# ProProject_Buck-Boost_1_2024-04-13.net
KiCad netlist of a schematic drawn in EasyEDA Pro
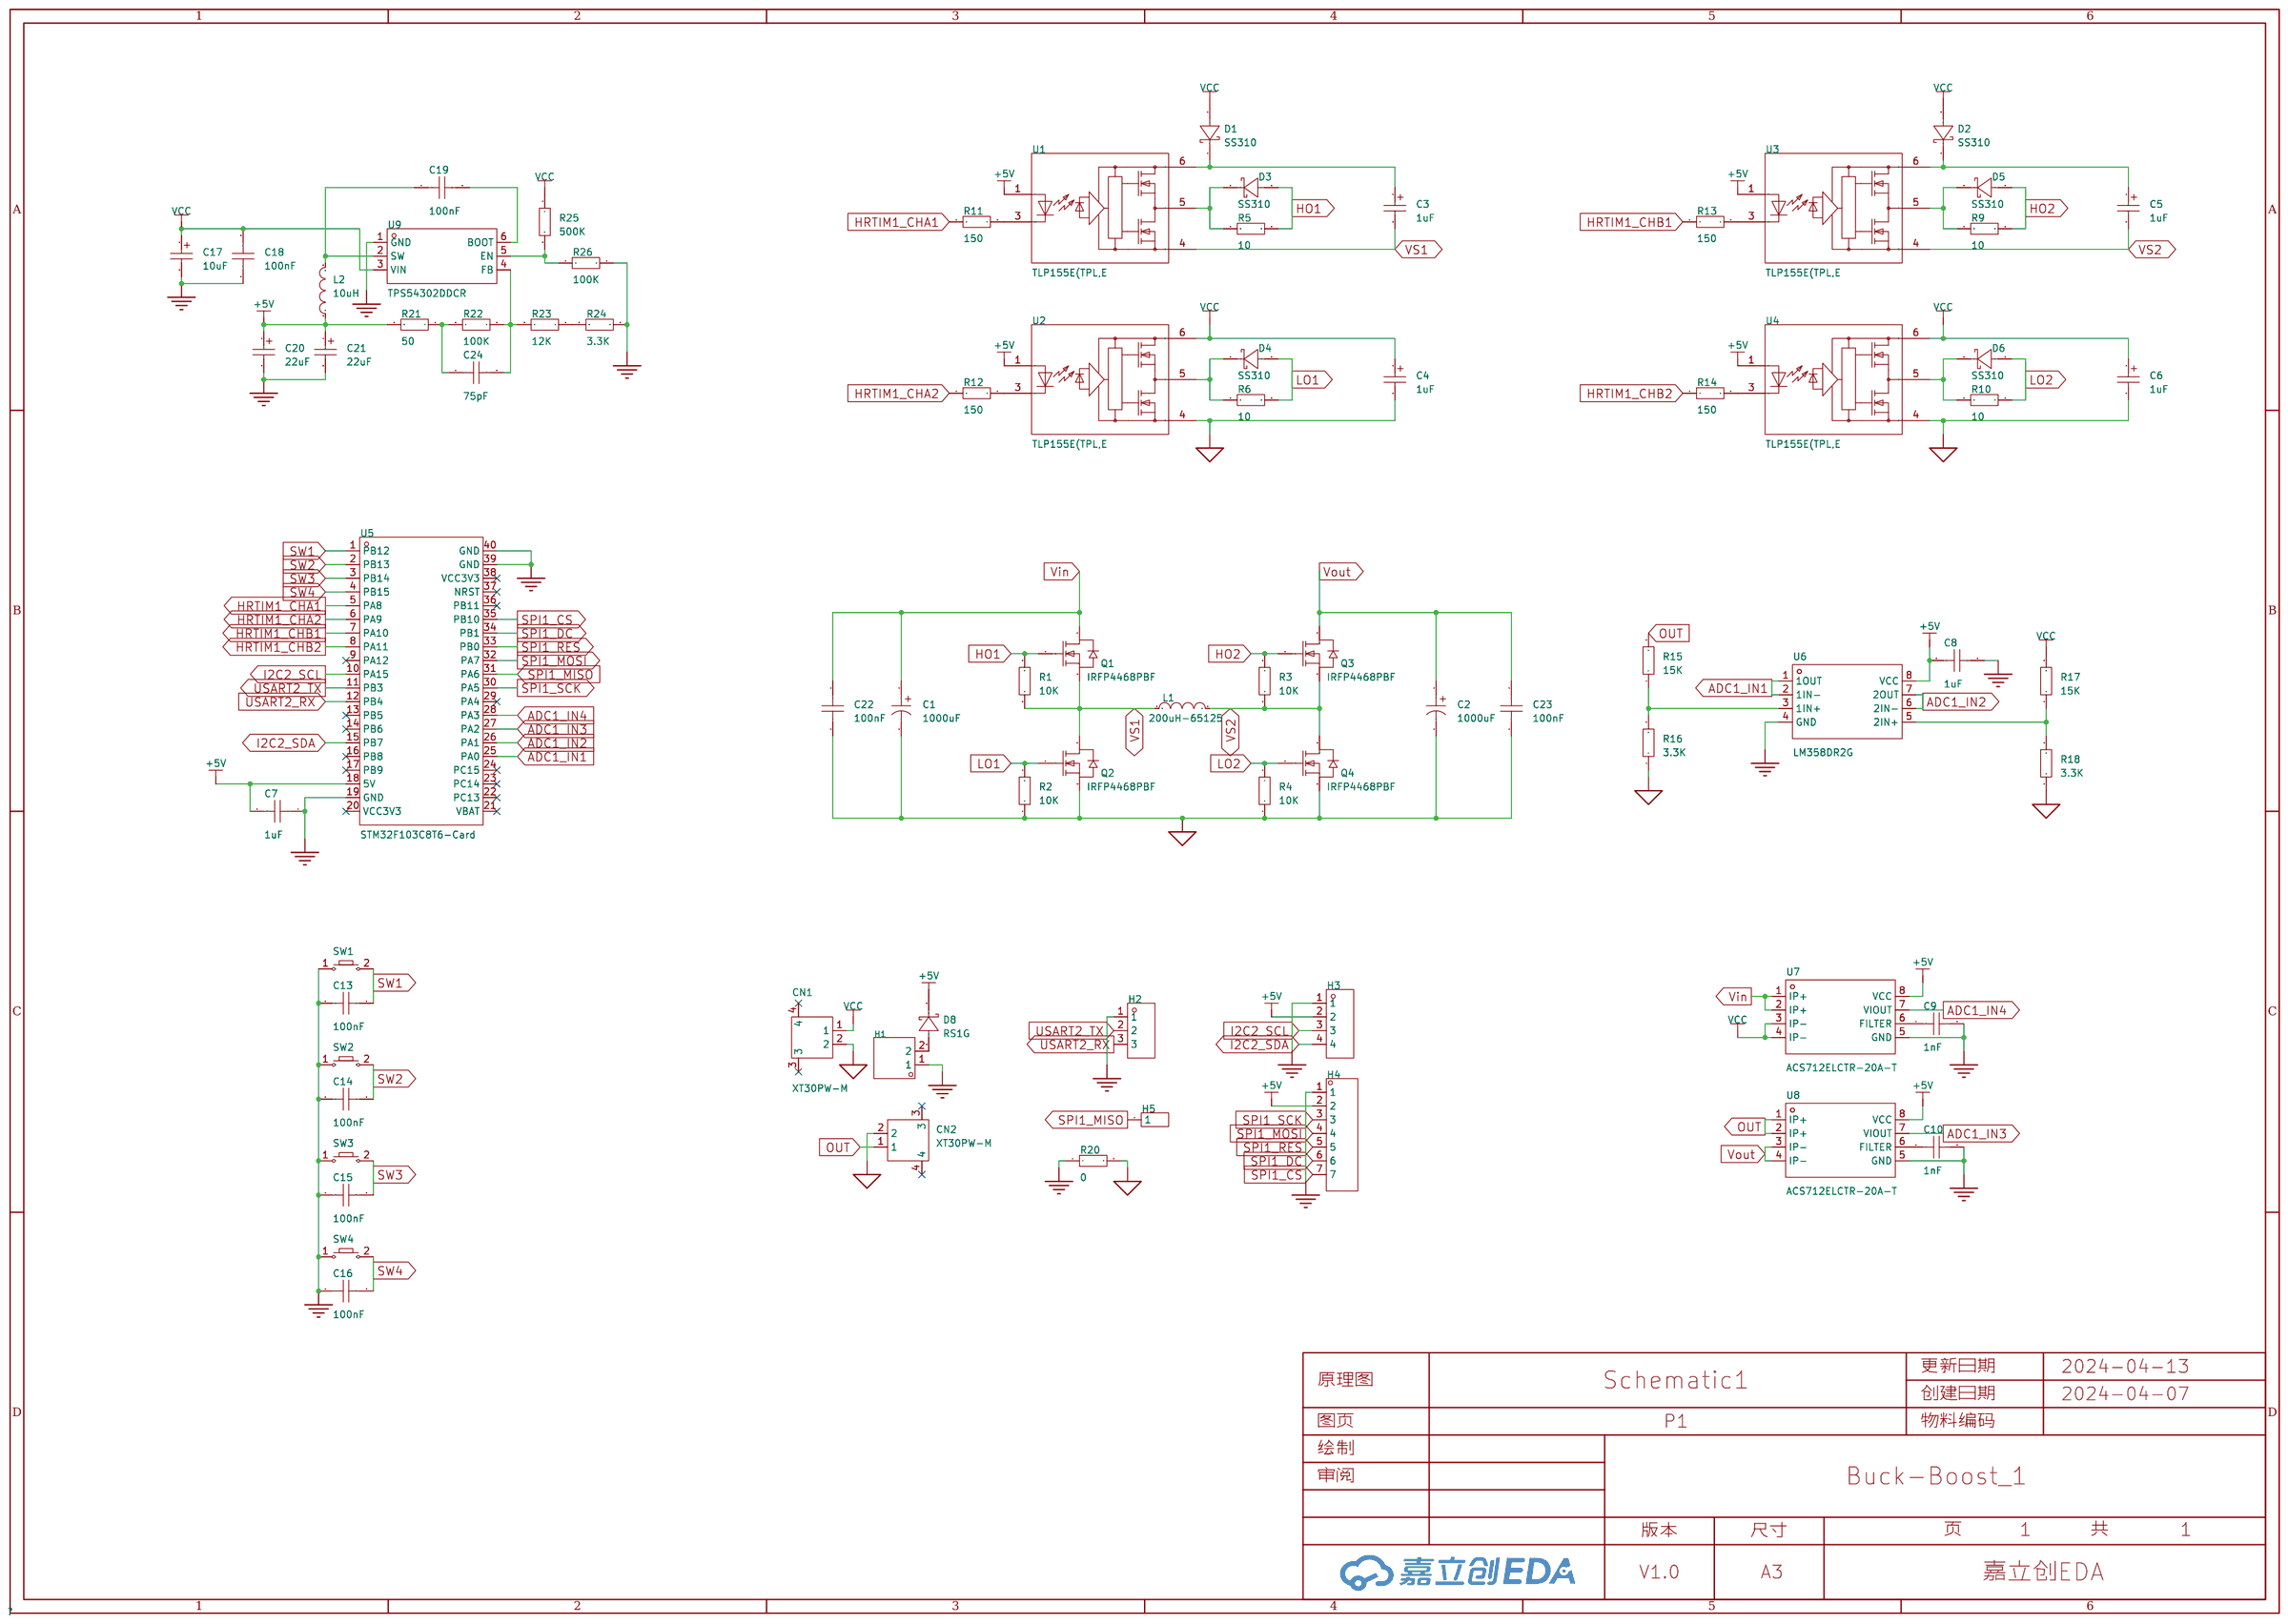
[diagram p0: schematic sheet]

(export (version "E")
  (design (tool "Eeschema 10.0.6"))
  (components
    (comp (ref "C1")
      (value "1000uF")
      (footprint "easyedapro:CAP-TH_BD16.0-P7.50-D1.5-FD")
      (description "容值:470uF;精度:±20%;额定电压:120V;纹波电流:-;等效串联电阻:-;")
      (fields (field (name "Manufacturer Part") "KF102M050I250A") (field (name "Manufacturer") "CapXon(丰宾)"))
      (libsource (lib "easyedapro") (part "ERS2BM471L35OT"))
    )
    (comp (ref "C2")
      (value "1000uF")
      (footprint "easyedapro:CAP-TH_BD16.0-P7.50-D1.5-FD")
      (description "容值:470uF;精度:±20%;额定电压:120V;纹波电流:-;等效串联电阻:-;")
      (fields (field (name "Manufacturer Part") "KF102M050I250A") (field (name "Manufacturer") "CapXon(丰宾)"))
      (libsource (lib "easyedapro") (part "ERS2BM471L35OT"))
    )
    (comp (ref "C3")
      (value "1uF")
      (footprint "easyedapro:CASE-A_3216")
      (description "容值:1uF;精度:±10%;额定电压:35V;等效串联电阻:7.5Ω@100kHz;")
      (fields (field (name "Manufacturer Part") "TAJA105K035RNJ") (field (name "Manufacturer") "Kyocera AVX"))
      (libsource (lib "easyedapro") (part "TAJA105K035RNJ"))
    )
    (comp (ref "C4")
      (value "1uF")
      (footprint "easyedapro:CASE-A_3216")
      (description "容值:1uF;精度:±10%;额定电压:35V;等效串联电阻:7.5Ω@100kHz;")
      (fields (field (name "Manufacturer Part") "TAJA105K035RNJ") (field (name "Manufacturer") "Kyocera AVX"))
      (libsource (lib "easyedapro") (part "TAJA105K035RNJ"))
    )
    (comp (ref "C5")
      (value "1uF")
      (footprint "easyedapro:CASE-A_3216")
      (description "容值:1uF;精度:±10%;额定电压:35V;等效串联电阻:7.5Ω@100kHz;")
      (fields (field (name "Manufacturer Part") "TAJA105K035RNJ") (field (name "Manufacturer") "Kyocera AVX"))
      (libsource (lib "easyedapro") (part "TAJA105K035RNJ"))
    )
    (comp (ref "C6")
      (value "1uF")
      (footprint "easyedapro:CASE-A_3216")
      (description "容值:1uF;精度:±10%;额定电压:35V;等效串联电阻:7.5Ω@100kHz;")
      (fields (field (name "Manufacturer Part") "TAJA105K035RNJ") (field (name "Manufacturer") "Kyocera AVX"))
      (libsource (lib "easyedapro") (part "TAJA105K035RNJ"))
    )
    (comp (ref "C7")
      (value "1uF")
      (footprint "easyedapro:C0805")
      (libsource (lib "easyedapro") (part "CapAcitance"))
    )
    (comp (ref "C8")
      (value "1uF")
      (footprint "easyedapro:C0805")
      (libsource (lib "easyedapro") (part "CapAcitance"))
    )
    (comp (ref "C9")
      (value "1nF")
      (footprint "easyedapro:C0805")
      (libsource (lib "easyedapro") (part "CapAcitance"))
    )
    (comp (ref "C10")
      (value "1nF")
      (footprint "easyedapro:C0805")
      (libsource (lib "easyedapro") (part "CapAcitance"))
    )
    (comp (ref "C13")
      (value "100nF")
      (footprint "easyedapro:C0805")
      (libsource (lib "easyedapro") (part "CapAcitance"))
    )
    (comp (ref "C14")
      (value "100nF")
      (footprint "easyedapro:C0805")
      (libsource (lib "easyedapro") (part "CapAcitance"))
    )
    (comp (ref "C15")
      (value "100nF")
      (footprint "easyedapro:C0805")
      (libsource (lib "easyedapro") (part "CapAcitance"))
    )
    (comp (ref "C16")
      (value "100nF")
      (footprint "easyedapro:C0805")
      (libsource (lib "easyedapro") (part "CapAcitance"))
    )
    (comp (ref "C17")
      (value "10uF")
      (footprint "easyedapro:CAP-SMD_L3.5-W2.8-R-RD")
      (description "容值:10uF;精度:±10%;额定电压:25V;等效串联电阻:2.5Ω@100kHz;")
      (fields (field (name "Manufacturer Part") "TAJB106K025RNJ") (field (name "Manufacturer") "Kyocera AVX"))
      (libsource (lib "easyedapro") (part "TAJB106K025RNJ"))
    )
    (comp (ref "C18")
      (value "100nF")
      (footprint "easyedapro:C0805")
      (libsource (lib "easyedapro") (part "CapAcitance"))
    )
    (comp (ref "C19")
      (value "100nF")
      (footprint "easyedapro:C0805")
      (libsource (lib "easyedapro") (part "CapAcitance"))
    )
    (comp (ref "C20")
      (value "22uF")
      (footprint "easyedapro:CASE-B_3528")
      (description "容值:22uF;精度:±10%;额定电压:16V;等效串联电阻:2.3Ω@100kHz;")
      (fields (field (name "Manufacturer Part") "TAJB226K016RNJ") (field (name "Manufacturer") "Kyocera AVX"))
      (libsource (lib "easyedapro") (part "TAJB226K016RNJ"))
    )
    (comp (ref "C21")
      (value "22uF")
      (footprint "easyedapro:CASE-B_3528")
      (description "容值:22uF;精度:±10%;额定电压:16V;等效串联电阻:2.3Ω@100kHz;")
      (fields (field (name "Manufacturer Part") "TAJB226K016RNJ") (field (name "Manufacturer") "Kyocera AVX"))
      (libsource (lib "easyedapro") (part "TAJB226K016RNJ"))
    )
    (comp (ref "C22")
      (value "100nF")
      (footprint "easyedapro:C0805")
      (libsource (lib "easyedapro") (part "CapAcitance"))
    )
    (comp (ref "C23")
      (value "100nF")
      (footprint "easyedapro:C0805")
      (libsource (lib "easyedapro") (part "CapAcitance"))
    )
    (comp (ref "C24")
      (value "75pF")
      (footprint "easyedapro:C0805")
      (libsource (lib "easyedapro") (part "CapAcitance"))
    )
    (comp (ref "CN1")
      (value "XT30PW-M")
      (footprint "easyedapro:CONN-TH_XT30PW-M")
      (description "类别:-;类型1:-;")
      (fields (field (name "Manufacturer") "AMASS(艾迈斯)"))
      (libsource (lib "easyedapro") (part "XT30PW-M"))
    )
    (comp (ref "CN2")
      (value "XT30PW-M")
      (footprint "easyedapro:CONN-TH_XT30PW-M")
      (description "类别:-;类型1:-;")
      (fields (field (name "Manufacturer") "AMASS(艾迈斯)"))
      (libsource (lib "easyedapro") (part "XT30PW-M"))
    )
    (comp (ref "D1")
      (value "SS310")
      (footprint "easyedapro:SMC_L6.9-W5.9-LS7.9-RD")
      (fields (field (name "Manufacturer") "MDD"))
      (libsource (lib "easyedapro") (part "SS56_C5161914"))
    )
    (comp (ref "D2")
      (value "SS310")
      (footprint "easyedapro:SMC_L6.9-W5.9-LS7.9-RD")
      (fields (field (name "Manufacturer") "MDD"))
      (libsource (lib "easyedapro") (part "SS56_C5161914"))
    )
    (comp (ref "D3")
      (value "SS310")
      (footprint "easyedapro:SMC_L6.9-W5.9-LS7.9-RD")
      (fields (field (name "Manufacturer") "MDD"))
      (libsource (lib "easyedapro") (part "SS56_C5161914"))
    )
    (comp (ref "D4")
      (value "SS310")
      (footprint "easyedapro:SMC_L6.9-W5.9-LS7.9-RD")
      (fields (field (name "Manufacturer") "MDD"))
      (libsource (lib "easyedapro") (part "SS56_C5161914"))
    )
    (comp (ref "D5")
      (value "SS310")
      (footprint "easyedapro:SMC_L6.9-W5.9-LS7.9-RD")
      (fields (field (name "Manufacturer") "MDD"))
      (libsource (lib "easyedapro") (part "SS56_C5161914"))
    )
    (comp (ref "D6")
      (value "SS310")
      (footprint "easyedapro:SMC_L6.9-W5.9-LS7.9-RD")
      (fields (field (name "Manufacturer") "MDD"))
      (libsource (lib "easyedapro") (part "SS56_C5161914"))
    )
    (comp (ref "D8")
      (value "RS1G")
      (footprint "easyedapro:SMC_L6.9-W5.9-LS7.9-RD")
      (fields (field (name "Manufacturer") "宏迦橙"))
      (libsource (lib "easyedapro") (part "SS56_C5161914"))
    )
    (comp (ref "H1")
      (value "~")
      (footprint "easyedapro:HDR-TH_2P-P2.54-V-M-1")
      (libsource (lib "easyedapro") (part "210S-1*2P L=11.6MMGold-plated black"))
    )
    (comp (ref "H2")
      (value "~")
      (footprint "easyedapro:HDR-TH_3P-P2.54-V-M")
      (libsource (lib "easyedapro") (part "PZ254V-11-03P_C2937625"))
    )
    (comp (ref "H3")
      (value "~")
      (footprint "easyedapro:HDR-TH_4P-P2.54-V-F")
      (libsource (lib "easyedapro") (part "2.54-1*4P母"))
    )
    (comp (ref "H4")
      (value "~")
      (footprint "easyedapro:HDR-TH_7P-P2.54-V-F")
      (libsource (lib "easyedapro") (part "220S-1*7P H=8.5MM Ytype Gold-plated"))
    )
    (comp (ref "H5")
      (value "~")
      (footprint "easyedapro:HDR-TH_1P-V-M_XKB_X4611WV-01I-C28D40")
      (libsource (lib "easyedapro") (part "HDR_1x1"))
    )
    (comp (ref "L1")
      (value "200uH-65125")
      (footprint "easyedapro:IND-TH_200UH-65125")
      (libsource (lib "easyedapro") (part "200UH-65125"))
    )
    (comp (ref "L2")
      (value "10uH")
      (footprint "easyedapro:IND-SMD_L7.3-W6.8")
      (description "电感值:10uH;精度:±20%;额定电流:4.5A;饱和电流(Isat):5.5A;类型:一体成型电感;")
      (fields (field (name "Manufacturer Part") "FXL0420-100-M") (field (name "Manufacturer") "cjiang(长江微电)"))
      (libsource (lib "easyedapro") (part "FXL0630-100-M"))
    )
    (comp (ref "Q1")
      (value "IRFP4468PBF")
      (footprint "easyedapro:TO-247AC-3_L15.8-W5.0-P5.46-L")
      (fields (field (name "Manufacturer") "Infineon(英飞凌)"))
      (libsource (lib "easyedapro") (part "IRFP4468PBF"))
    )
    (comp (ref "Q2")
      (value "IRFP4468PBF")
      (footprint "easyedapro:TO-247AC-3_L15.8-W5.0-P5.46-L")
      (fields (field (name "Manufacturer") "Infineon(英飞凌)"))
      (libsource (lib "easyedapro") (part "IRFP4468PBF"))
    )
    (comp (ref "Q3")
      (value "IRFP4468PBF")
      (footprint "easyedapro:TO-247AC-3_L15.8-W5.0-P5.46-L")
      (fields (field (name "Manufacturer") "Infineon(英飞凌)"))
      (libsource (lib "easyedapro") (part "IRFP4468PBF"))
    )
    (comp (ref "Q4")
      (value "IRFP4468PBF")
      (footprint "easyedapro:TO-247AC-3_L15.8-W5.0-P5.46-L")
      (fields (field (name "Manufacturer") "Infineon(英飞凌)"))
      (libsource (lib "easyedapro") (part "IRFP4468PBF"))
    )
    (comp (ref "R1") (value "10K") (footprint "easyedapro:R0805") (libsource (lib "easyedapro") (part "电阻")))
    (comp (ref "R2") (value "10K") (footprint "easyedapro:R0805") (libsource (lib "easyedapro") (part "电阻")))
    (comp (ref "R3") (value "10K") (footprint "easyedapro:R0805") (libsource (lib "easyedapro") (part "电阻")))
    (comp (ref "R4") (value "10K") (footprint "easyedapro:R0805") (libsource (lib "easyedapro") (part "电阻")))
    (comp (ref "R5") (value "10") (footprint "easyedapro:R0805") (libsource (lib "easyedapro") (part "电阻")))
    (comp (ref "R6") (value "10") (footprint "easyedapro:R0805") (libsource (lib "easyedapro") (part "电阻")))
    (comp (ref "R9") (value "10") (footprint "easyedapro:R0805") (libsource (lib "easyedapro") (part "电阻")))
    (comp (ref "R10") (value "10") (footprint "easyedapro:R0805") (libsource (lib "easyedapro") (part "电阻")))
    (comp (ref "R11") (value "150") (footprint "easyedapro:R0805") (libsource (lib "easyedapro") (part "电阻")))
    (comp (ref "R12") (value "150") (footprint "easyedapro:R0805") (libsource (lib "easyedapro") (part "电阻")))
    (comp (ref "R13") (value "150") (footprint "easyedapro:R0805") (libsource (lib "easyedapro") (part "电阻")))
    (comp (ref "R14") (value "150") (footprint "easyedapro:R0805") (libsource (lib "easyedapro") (part "电阻")))
    (comp (ref "R15") (value "15K") (footprint "easyedapro:R0805") (libsource (lib "easyedapro") (part "电阻")))
    (comp (ref "R16")
      (value "3.3K")
      (footprint "easyedapro:R0805")
      (libsource (lib "easyedapro") (part "电阻"))
    )
    (comp (ref "R17") (value "15K") (footprint "easyedapro:R0805") (libsource (lib "easyedapro") (part "电阻")))
    (comp (ref "R18")
      (value "3.3K")
      (footprint "easyedapro:R0805")
      (libsource (lib "easyedapro") (part "电阻"))
    )
    (comp (ref "R20") (value "0") (footprint "easyedapro:R0805") (libsource (lib "easyedapro") (part "电阻")))
    (comp (ref "R21") (value "50") (footprint "easyedapro:R0805") (libsource (lib "easyedapro") (part "电阻")))
    (comp (ref "R22")
      (value "100K")
      (footprint "easyedapro:R0805")
      (libsource (lib "easyedapro") (part "电阻"))
    )
    (comp (ref "R23") (value "12K") (footprint "easyedapro:R0805") (libsource (lib "easyedapro") (part "电阻")))
    (comp (ref "R24")
      (value "3.3K")
      (footprint "easyedapro:R0805")
      (libsource (lib "easyedapro") (part "电阻"))
    )
    (comp (ref "R25")
      (value "500K")
      (footprint "easyedapro:R0805")
      (libsource (lib "easyedapro") (part "电阻"))
    )
    (comp (ref "R26")
      (value "100K")
      (footprint "easyedapro:R0805")
      (libsource (lib "easyedapro") (part "电阻"))
    )
    (comp (ref "SW1")
      (value "~")
      (footprint "easyedapro:Key_SMD_3x4x2")
      (libsource (lib "easyedapro") (part "轻触按键x2"))
    )
    (comp (ref "SW2")
      (value "~")
      (footprint "easyedapro:Key_SMD_3x4x2")
      (libsource (lib "easyedapro") (part "轻触按键x2"))
    )
    (comp (ref "SW3")
      (value "~")
      (footprint "easyedapro:Key_SMD_3x4x2")
      (libsource (lib "easyedapro") (part "轻触按键x2"))
    )
    (comp (ref "SW4")
      (value "~")
      (footprint "easyedapro:Key_SMD_3x4x2")
      (libsource (lib "easyedapro") (part "轻触按键x2"))
    )
    (comp (ref "U1")
      (value "TLP155E(TPL,E")
      (footprint "easyedapro:OPTO-SMD-5_L3.7-W4.6-P1.27-LS7.0-BR")
      (description "输入类型:DC;电源电压:10V~30V;共模瞬变抗扰度CMTI:15kV/us;传播延迟tpLH/tpHL:170ns；170ns;")
      (fields (field (name "Manufacturer") "TOSHIBA(东芝)"))
      (libsource (lib "easyedapro") (part "TLP155E(TPL,E"))
    )
    (comp (ref "U2")
      (value "TLP155E(TPL,E")
      (footprint "easyedapro:OPTO-SMD-5_L3.7-W4.6-P1.27-LS7.0-BR")
      (description "输入类型:DC;电源电压:10V~30V;共模瞬变抗扰度CMTI:15kV/us;传播延迟tpLH/tpHL:170ns；170ns;")
      (fields (field (name "Manufacturer") "TOSHIBA(东芝)"))
      (libsource (lib "easyedapro") (part "TLP155E(TPL,E"))
    )
    (comp (ref "U3")
      (value "TLP155E(TPL,E")
      (footprint "easyedapro:OPTO-SMD-5_L3.7-W4.6-P1.27-LS7.0-BR")
      (description "输入类型:DC;电源电压:10V~30V;共模瞬变抗扰度CMTI:15kV/us;传播延迟tpLH/tpHL:170ns；170ns;")
      (fields (field (name "Manufacturer") "TOSHIBA(东芝)"))
      (libsource (lib "easyedapro") (part "TLP155E(TPL,E"))
    )
    (comp (ref "U4")
      (value "TLP155E(TPL,E")
      (footprint "easyedapro:OPTO-SMD-5_L3.7-W4.6-P1.27-LS7.0-BR")
      (description "输入类型:DC;电源电压:10V~30V;共模瞬变抗扰度CMTI:15kV/us;传播延迟tpLH/tpHL:170ns；170ns;")
      (fields (field (name "Manufacturer") "TOSHIBA(东芝)"))
      (libsource (lib "easyedapro") (part "TLP155E(TPL,E"))
    )
    (comp (ref "U5")
      (value "STM32F103C8T6-Card")
      (footprint "easyedapro:CONN-TH_L53.3-W22.9_STM32F103C8T6-CARD")
      (libsource (lib "easyedapro") (part "STM32F103C8T6-CARD"))
    )
    (comp (ref "U6")
      (value "LM358DR2G")
      (footprint "easyedapro:SOIC-8_L5.0-W4.0-P1.27-LS6.0-BL")
      (description "放大器数:双路;增益带宽积(GBP):1MHz;输入偏置电流(Ib):45nA;压摆率(SR):-;带宽(-3db):-;")
      (fields (field (name "Manufacturer") "onsemi(安森美)"))
      (libsource (lib "easyedapro") (part "LM358DR2G"))
    )
    (comp (ref "U7")
      (value "ACS712ELCTR-20A-T")
      (footprint "easyedapro:SOIC-8_L4.9-W3.9-P1.27-LS6.0-BL")
      (description "电流测量范围:20A;灵敏度:100mV/A;")
      (fields (field (name "Manufacturer") "ALLEGRO(美国埃戈罗)"))
      (libsource (lib "easyedapro") (part "ACS712ELCTR-20A-T"))
    )
    (comp (ref "U8")
      (value "ACS712ELCTR-20A-T")
      (footprint "easyedapro:SOIC-8_L4.9-W3.9-P1.27-LS6.0-BL")
      (description "电流测量范围:20A;灵敏度:100mV/A;")
      (fields (field (name "Manufacturer") "ALLEGRO(美国埃戈罗)"))
      (libsource (lib "easyedapro") (part "ACS712ELCTR-20A-T"))
    )
    (comp (ref "U9")
      (value "TPS54302DDCR")
      (footprint "easyedapro:SOT-23-6_L2.9-W1.6-P0.95-LS2.8-BL")
      (description "功能类型:降压型;输出类型:可调;输入电压:4.5V~28V;输出电压:596mV~28V;输出电流(最大值):3A;")
      (fields (field (name "Manufacturer") "TI(德州仪器)"))
      (libsource (lib "easyedapro") (part "TPS54302DDCR_C311983"))
    )
  )
  (nets
    (net (code "1") (name "+5V") (class "Default")
      (node (ref "C20") (pin "1") (pinfunction "1_1") (pintype "input"))
      (node (ref "C21") (pin "1") (pinfunction "1_1") (pintype "input"))
      (node (ref "C7") (pin "2") (pinfunction "2_2") (pintype "input"))
      (node (ref "C8") (pin "1") (pinfunction "1_1") (pintype "input"))
      (node (ref "D8") (pin "1") (pinfunction "K_1") (pintype "unspecified"))
      (node (ref "H3") (pin "2") (pinfunction "2_2") (pintype "unspecified"))
      (node (ref "H4") (pin "2") (pinfunction "2_2") (pintype "unspecified"))
      (node (ref "L2") (pin "1") (pinfunction "1_1") (pintype "unspecified"))
      (node (ref "R21") (pin "2") (pinfunction "2_2") (pintype "input"))
      (node (ref "U1") (pin "1") (pinfunction "AN_1") (pintype "unspecified"))
      (node (ref "U2") (pin "1") (pinfunction "AN_1") (pintype "unspecified"))
      (node (ref "U3") (pin "1") (pinfunction "AN_1") (pintype "unspecified"))
      (node (ref "U4") (pin "1") (pinfunction "AN_1") (pintype "unspecified"))
      (node (ref "U5") (pin "18") (pinfunction "5V_18") (pintype "unspecified"))
      (node (ref "U6") (pin "8") (pinfunction "VCC_8") (pintype "unspecified"))
      (node (ref "U7") (pin "8") (pinfunction "VCC_8") (pintype "unspecified"))
      (node (ref "U8") (pin "8") (pinfunction "VCC_8") (pintype "unspecified"))
    )
    (net (code "2") (name "ADC1_IN1") (class "Default")
      (node (ref "U5") (pin "25") (pinfunction "PA0_25") (pintype "unspecified"))
      (node (ref "U6") (pin "1") (pinfunction "1OUT_1") (pintype "unspecified"))
      (node (ref "U6") (pin "2") (pinfunction "1IN-_2") (pintype "unspecified"))
    )
    (net (code "3") (name "ADC1_IN2") (class "Default")
      (node (ref "U5") (pin "26") (pinfunction "PA1_26") (pintype "unspecified"))
      (node (ref "U6") (pin "6") (pinfunction "2IN-_6") (pintype "unspecified"))
      (node (ref "U6") (pin "7") (pinfunction "2OUT_7") (pintype "unspecified"))
    )
    (net (code "4") (name "ADC1_IN3") (class "Default")
      (node (ref "U5") (pin "27") (pinfunction "PA2_27") (pintype "unspecified"))
      (node (ref "U8") (pin "7") (pinfunction "VIOUT_7") (pintype "unspecified"))
    )
    (net (code "5") (name "ADC1_IN4") (class "Default")
      (node (ref "U5") (pin "28") (pinfunction "PA3_28") (pintype "unspecified"))
      (node (ref "U7") (pin "7") (pinfunction "VIOUT_7") (pintype "unspecified"))
    )
    (net (code "6") (name "AGND") (class "Default")
      (node (ref "C1") (pin "2") (pinfunction "2_2") (pintype "input"))
      (node (ref "C2") (pin "2") (pinfunction "2_2") (pintype "input"))
      (node (ref "C22") (pin "2") (pinfunction "2_2") (pintype "input"))
      (node (ref "C23") (pin "2") (pinfunction "2_2") (pintype "input"))
      (node (ref "C4") (pin "2") (pinfunction "2_2") (pintype "input"))
      (node (ref "C6") (pin "2") (pinfunction "2_2") (pintype "input"))
      (node (ref "CN1") (pin "2") (pinfunction "2_2") (pintype "unspecified"))
      (node (ref "CN2") (pin "2") (pinfunction "2_2") (pintype "unspecified"))
      (node (ref "Q2") (pin "3") (pinfunction "S_3") (pintype "unspecified"))
      (node (ref "Q4") (pin "3") (pinfunction "S_3") (pintype "unspecified"))
      (node (ref "R16") (pin "1") (pinfunction "1_1") (pintype "input"))
      (node (ref "R18") (pin "1") (pinfunction "1_1") (pintype "input"))
      (node (ref "R2") (pin "1") (pinfunction "1_1") (pintype "input"))
      (node (ref "R20") (pin "2") (pinfunction "2_2") (pintype "input"))
      (node (ref "R4") (pin "1") (pinfunction "1_1") (pintype "input"))
      (node (ref "U2") (pin "4") (pinfunction "GND_4") (pintype "unspecified"))
      (node (ref "U4") (pin "4") (pinfunction "GND_4") (pintype "unspecified"))
    )
    (net (code "7") (name "GND") (class "Default")
      (node (ref "C10") (pin "2") (pinfunction "2_2") (pintype "input"))
      (node (ref "C13") (pin "1") (pinfunction "1_1") (pintype "input"))
      (node (ref "C14") (pin "1") (pinfunction "1_1") (pintype "input"))
      (node (ref "C15") (pin "1") (pinfunction "1_1") (pintype "input"))
      (node (ref "C16") (pin "1") (pinfunction "1_1") (pintype "input"))
      (node (ref "C17") (pin "2") (pinfunction "2_2") (pintype "input"))
      (node (ref "C18") (pin "1") (pinfunction "1_1") (pintype "input"))
      (node (ref "C20") (pin "2") (pinfunction "2_2") (pintype "input"))
      (node (ref "C21") (pin "2") (pinfunction "2_2") (pintype "input"))
      (node (ref "C7") (pin "1") (pinfunction "1_1") (pintype "input"))
      (node (ref "C8") (pin "2") (pinfunction "2_2") (pintype "input"))
      (node (ref "C9") (pin "2") (pinfunction "2_2") (pintype "input"))
      (node (ref "H1") (pin "1") (pinfunction "1_1") (pintype "input"))
      (node (ref "H2") (pin "1") (pinfunction "1_1") (pintype "input"))
      (node (ref "H3") (pin "1") (pinfunction "1_1") (pintype "unspecified"))
      (node (ref "H4") (pin "1") (pinfunction "1_1") (pintype "unspecified"))
      (node (ref "R20") (pin "1") (pinfunction "1_1") (pintype "input"))
      (node (ref "R24") (pin "2") (pinfunction "2_2") (pintype "input"))
      (node (ref "R26") (pin "2") (pinfunction "2_2") (pintype "input"))
      (node (ref "SW1") (pin "1") (pinfunction "1_1") (pintype "input"))
      (node (ref "SW2") (pin "1") (pinfunction "1_1") (pintype "input"))
      (node (ref "SW3") (pin "1") (pinfunction "1_1") (pintype "input"))
      (node (ref "SW4") (pin "1") (pinfunction "1_1") (pintype "input"))
      (node (ref "U5") (pin "19") (pinfunction "GND_19") (pintype "unspecified"))
      (node (ref "U5") (pin "39") (pinfunction "GND_39") (pintype "unspecified"))
      (node (ref "U5") (pin "40") (pinfunction "GND_40") (pintype "unspecified"))
      (node (ref "U6") (pin "4") (pinfunction "GND_4") (pintype "unspecified"))
      (node (ref "U7") (pin "5") (pinfunction "GND_5") (pintype "unspecified"))
      (node (ref "U8") (pin "5") (pinfunction "GND_5") (pintype "unspecified"))
      (node (ref "U9") (pin "1") (pinfunction "GND_1") (pintype "unspecified"))
    )
    (net (code "8") (name "HO1") (class "Default")
      (node (ref "D3") (pin "2") (pinfunction "A_2") (pintype "unspecified"))
      (node (ref "Q1") (pin "1") (pinfunction "G_1") (pintype "unspecified"))
      (node (ref "R1") (pin "2") (pinfunction "2_2") (pintype "input"))
      (node (ref "R5") (pin "2") (pinfunction "2_2") (pintype "input"))
    )
    (net (code "9") (name "HO2") (class "Default")
      (node (ref "D5") (pin "2") (pinfunction "A_2") (pintype "unspecified"))
      (node (ref "Q3") (pin "1") (pinfunction "G_1") (pintype "unspecified"))
      (node (ref "R3") (pin "2") (pinfunction "2_2") (pintype "input"))
      (node (ref "R9") (pin "2") (pinfunction "2_2") (pintype "input"))
    )
    (net (code "10") (name "HRTIM1_CHA1") (class "Default")
      (node (ref "R11") (pin "1") (pinfunction "1_1") (pintype "input"))
      (node (ref "U5") (pin "5") (pinfunction "PA8_5") (pintype "unspecified"))
    )
    (net (code "11") (name "HRTIM1_CHA2") (class "Default")
      (node (ref "R12") (pin "1") (pinfunction "1_1") (pintype "input"))
      (node (ref "U5") (pin "6") (pinfunction "PA9_6") (pintype "unspecified"))
    )
    (net (code "12") (name "HRTIM1_CHB1") (class "Default")
      (node (ref "R13") (pin "1") (pinfunction "1_1") (pintype "input"))
      (node (ref "U5") (pin "7") (pinfunction "PA10_7") (pintype "unspecified"))
    )
    (net (code "13") (name "HRTIM1_CHB2") (class "Default")
      (node (ref "R14") (pin "1") (pinfunction "1_1") (pintype "input"))
      (node (ref "U5") (pin "8") (pinfunction "PA11_8") (pintype "unspecified"))
    )
    (net (code "14") (name "I2C2_SCL") (class "Default")
      (node (ref "H3") (pin "3") (pinfunction "3_3") (pintype "unspecified"))
      (node (ref "U5") (pin "10") (pinfunction "PA15_10") (pintype "unspecified"))
    )
    (net (code "15") (name "I2C2_SDA") (class "Default")
      (node (ref "H3") (pin "4") (pinfunction "4_4") (pintype "unspecified"))
      (node (ref "U5") (pin "15") (pinfunction "PB7_15") (pintype "unspecified"))
    )
    (net (code "16") (name "LO1") (class "Default")
      (node (ref "D4") (pin "2") (pinfunction "A_2") (pintype "unspecified"))
      (node (ref "Q2") (pin "1") (pinfunction "G_1") (pintype "unspecified"))
      (node (ref "R2") (pin "2") (pinfunction "2_2") (pintype "input"))
      (node (ref "R6") (pin "2") (pinfunction "2_2") (pintype "input"))
    )
    (net (code "17") (name "LO2") (class "Default")
      (node (ref "D6") (pin "2") (pinfunction "A_2") (pintype "unspecified"))
      (node (ref "Q4") (pin "1") (pinfunction "G_1") (pintype "unspecified"))
      (node (ref "R10") (pin "2") (pinfunction "2_2") (pintype "input"))
      (node (ref "R4") (pin "2") (pinfunction "2_2") (pintype "input"))
    )
    (net (code "18") (name "Net-(C24-Pad1)") (class "Default")
      (node (ref "C24") (pin "1") (pinfunction "1_1") (pintype "input"))
      (node (ref "R21") (pin "1") (pinfunction "1_1") (pintype "input"))
      (node (ref "R22") (pin "2") (pinfunction "2_2") (pintype "input"))
    )
    (net (code "19") (name "Net-(D1-K)") (class "Default")
      (node (ref "C3") (pin "1") (pinfunction "1_1") (pintype "input"))
      (node (ref "D1") (pin "1") (pinfunction "K_1") (pintype "unspecified"))
      (node (ref "U1") (pin "6") (pinfunction "VCC_6") (pintype "unspecified"))
    )
    (net (code "20") (name "Net-(D2-K)") (class "Default")
      (node (ref "C5") (pin "1") (pinfunction "1_1") (pintype "input"))
      (node (ref "D2") (pin "1") (pinfunction "K_1") (pintype "unspecified"))
      (node (ref "U3") (pin "6") (pinfunction "VCC_6") (pintype "unspecified"))
    )
    (net (code "21") (name "Net-(D3-K)") (class "Default")
      (node (ref "D3") (pin "1") (pinfunction "K_1") (pintype "unspecified"))
      (node (ref "R5") (pin "1") (pinfunction "1_1") (pintype "input"))
      (node (ref "U1") (pin "5") (pinfunction "VO_5") (pintype "unspecified"))
    )
    (net (code "22") (name "Net-(D4-K)") (class "Default")
      (node (ref "D4") (pin "1") (pinfunction "K_1") (pintype "unspecified"))
      (node (ref "R6") (pin "1") (pinfunction "1_1") (pintype "input"))
      (node (ref "U2") (pin "5") (pinfunction "VO_5") (pintype "unspecified"))
    )
    (net (code "23") (name "Net-(D5-K)") (class "Default")
      (node (ref "D5") (pin "1") (pinfunction "K_1") (pintype "unspecified"))
      (node (ref "R9") (pin "1") (pinfunction "1_1") (pintype "input"))
      (node (ref "U3") (pin "5") (pinfunction "VO_5") (pintype "unspecified"))
    )
    (net (code "24") (name "Net-(D6-K)") (class "Default")
      (node (ref "D6") (pin "1") (pinfunction "K_1") (pintype "unspecified"))
      (node (ref "R10") (pin "1") (pinfunction "1_1") (pintype "input"))
      (node (ref "U4") (pin "5") (pinfunction "VO_5") (pintype "unspecified"))
    )
    (net (code "25") (name "Net-(D8-A)") (class "Default")
      (node (ref "D8") (pin "2") (pinfunction "A_2") (pintype "unspecified"))
      (node (ref "H1") (pin "2") (pinfunction "2_2") (pintype "input"))
    )
    (net (code "26") (name "Net-(R23-Pad1)") (class "Default")
      (node (ref "R23") (pin "1") (pinfunction "1_1") (pintype "input"))
      (node (ref "R24") (pin "1") (pinfunction "1_1") (pintype "input"))
    )
    (net (code "27") (name "Net-(U1-CAT)") (class "Default")
      (node (ref "R11") (pin "2") (pinfunction "2_2") (pintype "input"))
      (node (ref "U1") (pin "3") (pinfunction "CAT_3") (pintype "unspecified"))
    )
    (net (code "28") (name "Net-(U2-CAT)") (class "Default")
      (node (ref "R12") (pin "2") (pinfunction "2_2") (pintype "input"))
      (node (ref "U2") (pin "3") (pinfunction "CAT_3") (pintype "unspecified"))
    )
    (net (code "29") (name "Net-(U3-CAT)") (class "Default")
      (node (ref "R13") (pin "2") (pinfunction "2_2") (pintype "input"))
      (node (ref "U3") (pin "3") (pinfunction "CAT_3") (pintype "unspecified"))
    )
    (net (code "30") (name "Net-(U4-CAT)") (class "Default")
      (node (ref "R14") (pin "2") (pinfunction "2_2") (pintype "input"))
      (node (ref "U4") (pin "3") (pinfunction "CAT_3") (pintype "unspecified"))
    )
    (net (code "31") (name "Net-(U6-1IN+)") (class "Default")
      (node (ref "R15") (pin "1") (pinfunction "1_1") (pintype "input"))
      (node (ref "R16") (pin "2") (pinfunction "2_2") (pintype "input"))
      (node (ref "U6") (pin "3") (pinfunction "1IN+_3") (pintype "unspecified"))
    )
    (net (code "32") (name "Net-(U6-2IN+)") (class "Default")
      (node (ref "R17") (pin "1") (pinfunction "1_1") (pintype "input"))
      (node (ref "R18") (pin "2") (pinfunction "2_2") (pintype "input"))
      (node (ref "U6") (pin "5") (pinfunction "2IN+_5") (pintype "unspecified"))
    )
    (net (code "33") (name "Net-(U7-FILTER)") (class "Default")
      (node (ref "C9") (pin "1") (pinfunction "1_1") (pintype "input"))
      (node (ref "U7") (pin "6") (pinfunction "FILTER_6") (pintype "unspecified"))
    )
    (net (code "34") (name "Net-(U8-FILTER)") (class "Default")
      (node (ref "C10") (pin "1") (pinfunction "1_1") (pintype "input"))
      (node (ref "U8") (pin "6") (pinfunction "FILTER_6") (pintype "unspecified"))
    )
    (net (code "35") (name "Net-(U9-BOOT)") (class "Default")
      (node (ref "C19") (pin "2") (pinfunction "2_2") (pintype "input"))
      (node (ref "U9") (pin "6") (pinfunction "BOOT_6") (pintype "unspecified"))
    )
    (net (code "36") (name "Net-(U9-EN)") (class "Default")
      (node (ref "R25") (pin "2") (pinfunction "2_2") (pintype "input"))
      (node (ref "R26") (pin "1") (pinfunction "1_1") (pintype "input"))
      (node (ref "U9") (pin "5") (pinfunction "EN_5") (pintype "unspecified"))
    )
    (net (code "37") (name "Net-(U9-FB)") (class "Default")
      (node (ref "C24") (pin "2") (pinfunction "2_2") (pintype "input"))
      (node (ref "R22") (pin "1") (pinfunction "1_1") (pintype "input"))
      (node (ref "R23") (pin "2") (pinfunction "2_2") (pintype "input"))
      (node (ref "U9") (pin "4") (pinfunction "FB_4") (pintype "unspecified"))
    )
    (net (code "38") (name "Net-(U9-SW)") (class "Default")
      (node (ref "C19") (pin "1") (pinfunction "1_1") (pintype "input"))
      (node (ref "L2") (pin "2") (pinfunction "2_2") (pintype "unspecified"))
      (node (ref "U9") (pin "2") (pinfunction "SW_2") (pintype "unspecified"))
    )
    (net (code "39") (name "OUT") (class "Default")
      (node (ref "CN2") (pin "1") (pinfunction "1_1") (pintype "unspecified"))
      (node (ref "R15") (pin "2") (pinfunction "2_2") (pintype "input"))
      (node (ref "U8") (pin "1") (pinfunction "IP+_1") (pintype "unspecified"))
      (node (ref "U8") (pin "2") (pinfunction "IP+_2") (pintype "unspecified"))
    )
    (net (code "40") (name "SPI1_CS") (class "Default")
      (node (ref "H4") (pin "7") (pinfunction "7_7") (pintype "unspecified"))
      (node (ref "U5") (pin "35") (pinfunction "PB10_35") (pintype "unspecified"))
    )
    (net (code "41") (name "SPI1_DC") (class "Default")
      (node (ref "H4") (pin "6") (pinfunction "6_6") (pintype "unspecified"))
      (node (ref "U5") (pin "34") (pinfunction "PB1_34") (pintype "unspecified"))
    )
    (net (code "42") (name "SPI1_MISO") (class "Default")
      (node (ref "H5") (pin "1") (pinfunction "1_1") (pintype "unspecified"))
      (node (ref "U5") (pin "31") (pinfunction "PA6_31") (pintype "unspecified"))
    )
    (net (code "43") (name "SPI1_MOSI") (class "Default")
      (node (ref "H4") (pin "4") (pinfunction "4_4") (pintype "unspecified"))
      (node (ref "U5") (pin "32") (pinfunction "PA7_32") (pintype "unspecified"))
    )
    (net (code "44") (name "SPI1_RES") (class "Default")
      (node (ref "H4") (pin "5") (pinfunction "5_5") (pintype "unspecified"))
      (node (ref "U5") (pin "33") (pinfunction "PB0_33") (pintype "unspecified"))
    )
    (net (code "45") (name "SPI1_SCK") (class "Default")
      (node (ref "H4") (pin "3") (pinfunction "3_3") (pintype "unspecified"))
      (node (ref "U5") (pin "30") (pinfunction "PA5_30") (pintype "unspecified"))
    )
    (net (code "46") (name "SW1") (class "Default")
      (node (ref "C13") (pin "2") (pinfunction "2_2") (pintype "input"))
      (node (ref "SW1") (pin "2") (pinfunction "2_2") (pintype "input"))
      (node (ref "U5") (pin "1") (pinfunction "PB12_1") (pintype "unspecified"))
    )
    (net (code "47") (name "SW2") (class "Default")
      (node (ref "C14") (pin "2") (pinfunction "2_2") (pintype "input"))
      (node (ref "SW2") (pin "2") (pinfunction "2_2") (pintype "input"))
      (node (ref "U5") (pin "2") (pinfunction "PB13_2") (pintype "unspecified"))
    )
    (net (code "48") (name "SW3") (class "Default")
      (node (ref "C15") (pin "2") (pinfunction "2_2") (pintype "input"))
      (node (ref "SW3") (pin "2") (pinfunction "2_2") (pintype "input"))
      (node (ref "U5") (pin "3") (pinfunction "PB14_3") (pintype "unspecified"))
    )
    (net (code "49") (name "SW4") (class "Default")
      (node (ref "C16") (pin "2") (pinfunction "2_2") (pintype "input"))
      (node (ref "SW4") (pin "2") (pinfunction "2_2") (pintype "input"))
      (node (ref "U5") (pin "4") (pinfunction "PB15_4") (pintype "unspecified"))
    )
    (net (code "50") (name "USART2_RX") (class "Default")
      (node (ref "H2") (pin "3") (pinfunction "3_3") (pintype "input"))
      (node (ref "U5") (pin "12") (pinfunction "PB4_12") (pintype "unspecified"))
    )
    (net (code "51") (name "USART2_TX") (class "Default")
      (node (ref "H2") (pin "2") (pinfunction "2_2") (pintype "input"))
      (node (ref "U5") (pin "11") (pinfunction "PB3_11") (pintype "unspecified"))
    )
    (net (code "52") (name "VCC") (class "Default")
      (node (ref "C17") (pin "1") (pinfunction "1_1") (pintype "input"))
      (node (ref "C18") (pin "2") (pinfunction "2_2") (pintype "input"))
      (node (ref "C4") (pin "1") (pinfunction "1_1") (pintype "input"))
      (node (ref "C6") (pin "1") (pinfunction "1_1") (pintype "input"))
      (node (ref "CN1") (pin "1") (pinfunction "1_1") (pintype "unspecified"))
      (node (ref "D1") (pin "2") (pinfunction "A_2") (pintype "unspecified"))
      (node (ref "D2") (pin "2") (pinfunction "A_2") (pintype "unspecified"))
      (node (ref "R17") (pin "2") (pinfunction "2_2") (pintype "input"))
      (node (ref "R25") (pin "1") (pinfunction "1_1") (pintype "input"))
      (node (ref "U2") (pin "6") (pinfunction "VCC_6") (pintype "unspecified"))
      (node (ref "U4") (pin "6") (pinfunction "VCC_6") (pintype "unspecified"))
      (node (ref "U7") (pin "3") (pinfunction "IP-_3") (pintype "unspecified"))
      (node (ref "U7") (pin "4") (pinfunction "IP-_4") (pintype "unspecified"))
      (node (ref "U9") (pin "3") (pinfunction "VIN_3") (pintype "unspecified"))
    )
    (net (code "53") (name "VS1") (class "Default")
      (node (ref "C3") (pin "2") (pinfunction "2_2") (pintype "input"))
      (node (ref "L1") (pin "1") (pinfunction "1_1") (pintype "input"))
      (node (ref "Q1") (pin "3") (pinfunction "S_3") (pintype "unspecified"))
      (node (ref "Q2") (pin "2") (pinfunction "D_2") (pintype "unspecified"))
      (node (ref "R1") (pin "1") (pinfunction "1_1") (pintype "input"))
      (node (ref "U1") (pin "4") (pinfunction "GND_4") (pintype "unspecified"))
    )
    (net (code "54") (name "VS2") (class "Default")
      (node (ref "C5") (pin "2") (pinfunction "2_2") (pintype "input"))
      (node (ref "L1") (pin "2") (pinfunction "2_2") (pintype "input"))
      (node (ref "Q3") (pin "3") (pinfunction "S_3") (pintype "unspecified"))
      (node (ref "Q4") (pin "2") (pinfunction "D_2") (pintype "unspecified"))
      (node (ref "R3") (pin "1") (pinfunction "1_1") (pintype "input"))
      (node (ref "U3") (pin "4") (pinfunction "GND_4") (pintype "unspecified"))
    )
    (net (code "55") (name "Vin") (class "Default")
      (node (ref "C1") (pin "1") (pinfunction "1_1") (pintype "input"))
      (node (ref "C22") (pin "1") (pinfunction "1_1") (pintype "input"))
      (node (ref "Q1") (pin "2") (pinfunction "D_2") (pintype "unspecified"))
      (node (ref "U7") (pin "1") (pinfunction "IP+_1") (pintype "unspecified"))
      (node (ref "U7") (pin "2") (pinfunction "IP+_2") (pintype "unspecified"))
    )
    (net (code "56") (name "Vout") (class "Default")
      (node (ref "C2") (pin "1") (pinfunction "1_1") (pintype "input"))
      (node (ref "C23") (pin "1") (pinfunction "1_1") (pintype "input"))
      (node (ref "Q3") (pin "2") (pinfunction "D_2") (pintype "unspecified"))
      (node (ref "U8") (pin "3") (pinfunction "IP-_3") (pintype "unspecified"))
      (node (ref "U8") (pin "4") (pinfunction "IP-_4") (pintype "unspecified"))
    )
    (net (code "57") (name "unconnected-(CN1-Pad3)") (class "Default")
      (node (ref "CN1") (pin "3") (pinfunction "3_3") (pintype "unspecified+no_connect"))
    )
    (net (code "58") (name "unconnected-(CN1-Pad4)") (class "Default")
      (node (ref "CN1") (pin "4") (pinfunction "4_4") (pintype "unspecified+no_connect"))
    )
    (net (code "59") (name "unconnected-(CN2-Pad3)") (class "Default")
      (node (ref "CN2") (pin "3") (pinfunction "3_3") (pintype "unspecified+no_connect"))
    )
    (net (code "60") (name "unconnected-(CN2-Pad4)") (class "Default")
      (node (ref "CN2") (pin "4") (pinfunction "4_4") (pintype "unspecified+no_connect"))
    )
    (net (code "61") (name "unconnected-(U5-NRST-Pad37)") (class "Default")
      (node (ref "U5") (pin "37") (pinfunction "NRST_37") (pintype "unspecified+no_connect"))
    )
    (net (code "62") (name "unconnected-(U5-PA4-Pad29)") (class "Default")
      (node (ref "U5") (pin "29") (pinfunction "PA4_29") (pintype "unspecified+no_connect"))
    )
    (net (code "63") (name "unconnected-(U5-PA12-Pad9)") (class "Default")
      (node (ref "U5") (pin "9") (pinfunction "PA12_9") (pintype "unspecified+no_connect"))
    )
    (net (code "64") (name "unconnected-(U5-PB5-Pad13)") (class "Default")
      (node (ref "U5") (pin "13") (pinfunction "PB5_13") (pintype "unspecified+no_connect"))
    )
    (net (code "65") (name "unconnected-(U5-PB6-Pad14)") (class "Default")
      (node (ref "U5") (pin "14") (pinfunction "PB6_14") (pintype "unspecified+no_connect"))
    )
    (net (code "66") (name "unconnected-(U5-PB8-Pad16)") (class "Default")
      (node (ref "U5") (pin "16") (pinfunction "PB8_16") (pintype "unspecified+no_connect"))
    )
    (net (code "67") (name "unconnected-(U5-PB9-Pad17)") (class "Default")
      (node (ref "U5") (pin "17") (pinfunction "PB9_17") (pintype "unspecified+no_connect"))
    )
    (net (code "68") (name "unconnected-(U5-PB11-Pad36)") (class "Default")
      (node (ref "U5") (pin "36") (pinfunction "PB11_36") (pintype "unspecified+no_connect"))
    )
    (net (code "69") (name "unconnected-(U5-PC13-Pad22)") (class "Default")
      (node (ref "U5") (pin "22") (pinfunction "PC13_22") (pintype "unspecified+no_connect"))
    )
    (net (code "70") (name "unconnected-(U5-PC14-Pad23)") (class "Default")
      (node (ref "U5") (pin "23") (pinfunction "PC14_23") (pintype "unspecified+no_connect"))
    )
    (net (code "71") (name "unconnected-(U5-PC15-Pad24)") (class "Default")
      (node (ref "U5") (pin "24") (pinfunction "PC15_24") (pintype "unspecified+no_connect"))
    )
    (net (code "72") (name "unconnected-(U5-VBAT-Pad21)") (class "Default")
      (node (ref "U5") (pin "21") (pinfunction "VBAT_21") (pintype "unspecified+no_connect"))
    )
    (net (code "73") (name "unconnected-(U5-VCC3V3-Pad20)") (class "Default")
      (node (ref "U5") (pin "20") (pinfunction "VCC3V3_20") (pintype "unspecified+no_connect"))
    )
    (net (code "74") (name "unconnected-(U5-VCC3V3-Pad38)") (class "Default")
      (node (ref "U5") (pin "38") (pinfunction "VCC3V3_38") (pintype "unspecified+no_connect"))
    )
  )
)
